# Sheet1.net
KiCad netlist of a schematic drawn in Altium Designer
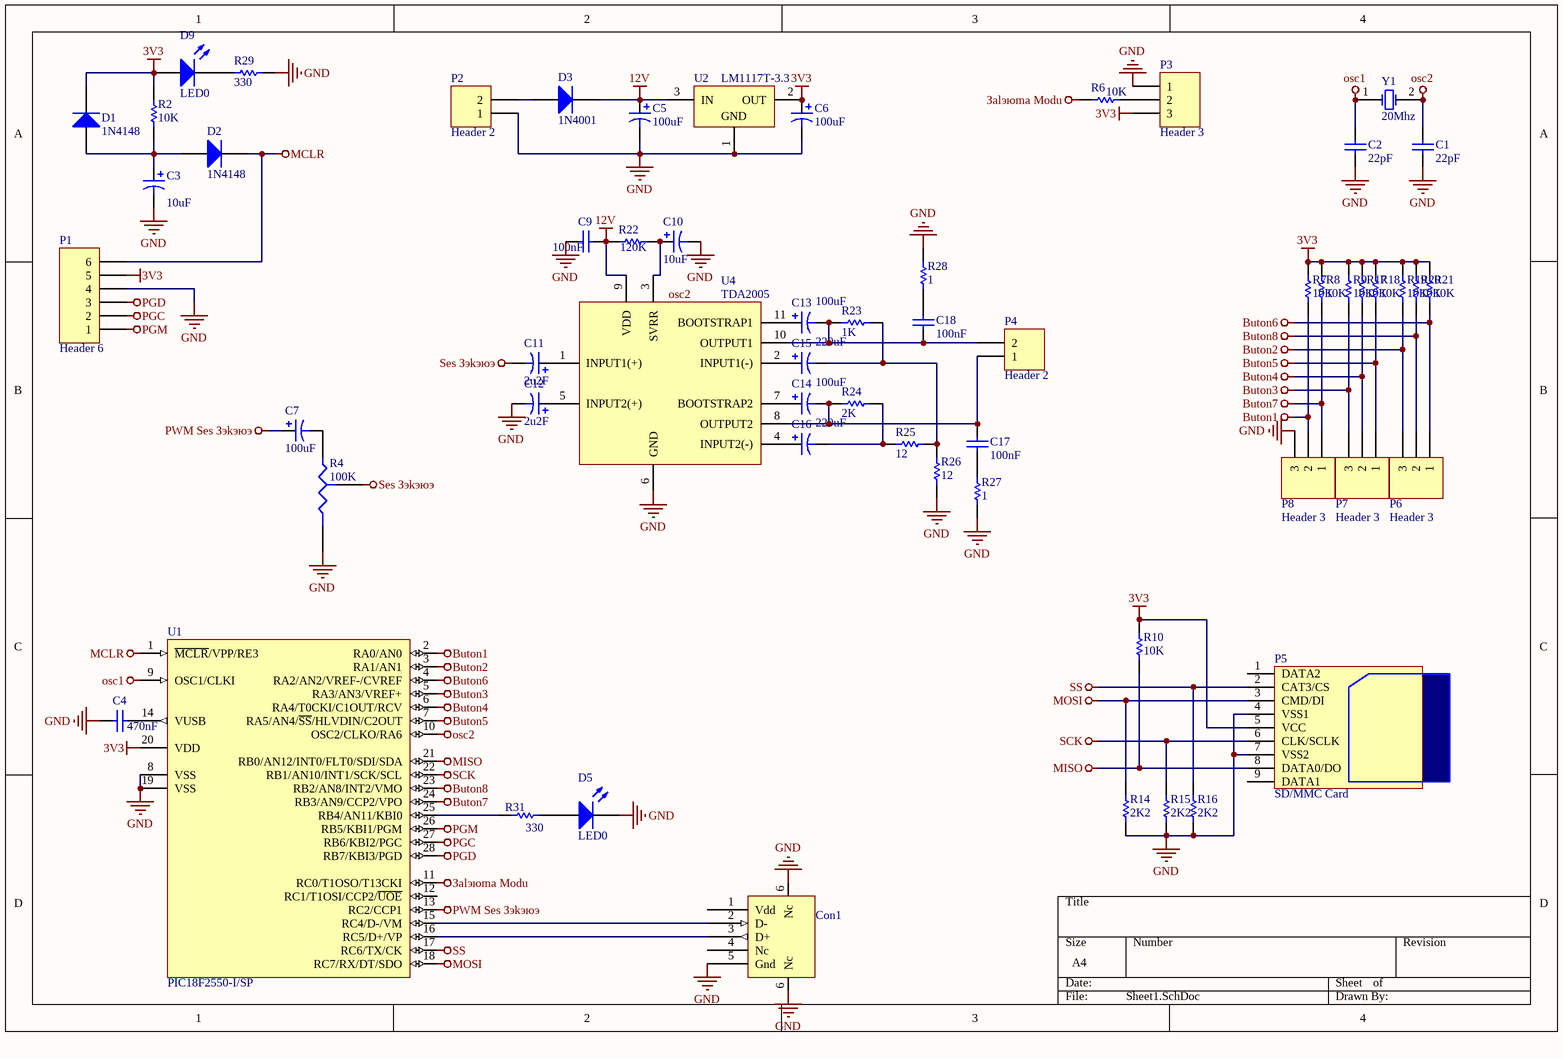
[diagram p0: Sheet1.SchDoc]

(export (version "E")
  (design (tool "Eeschema 10.0.6"))
  (components
    (comp (ref "C1")
      (value "22pF")
      (footprint "R38")
      (description "Capacitor")
      (fields (field (name "PUBLISHER") "Altium Limited"))
      (libsource (lib "Miscellaneous Devices") (part "Cap"))
    )
    (comp (ref "C2")
      (value "22pF")
      (footprint "R38")
      (description "Capacitor")
      (fields (field (name "PUBLISHER") "Altium Limited"))
      (libsource (lib "Miscellaneous Devices") (part "Cap"))
    )
    (comp (ref "C3")
      (value "10uF")
      (footprint "CAP 5x11 - 2mm")
      (description "Polarized Capacitor (Radial)")
      (fields (field (name "PUBLISHER") "Altium Limited"))
      (libsource (lib "Miscellaneous Devices") (part "Cap Pol1"))
    )
    (comp (ref "C4")
      (value "470nF")
      (footprint "Cap 5mm")
      (description "Capacitor")
      (fields (field (name "PUBLISHER") "Altium Limited"))
      (libsource (lib "Miscellaneous Devices") (part "Cap"))
    )
    (comp (ref "C5")
      (value "100uF")
      (footprint "Cap 8x11.5 - 3.5mm")
      (description "Polarized Capacitor (Radial)")
      (fields (field (name "PUBLISHER") "Altium Limited"))
      (libsource (lib "Miscellaneous Devices") (part "Cap Pol1"))
    )
    (comp (ref "C6")
      (value "100uF")
      (footprint "Cap 8x11.5 - 3.5mm")
      (description "Polarized Capacitor (Radial)")
      (fields (field (name "PUBLISHER") "Altium Limited"))
      (libsource (lib "Miscellaneous Devices") (part "Cap Pol1"))
    )
    (comp (ref "C7")
      (value "100uF")
      (footprint "Cap 8x11.5 - 3.5mm")
      (description "Polarized Capacitor (Radial)")
      (fields (field (name "PUBLISHER") "Altium Limited"))
      (libsource (lib "Miscellaneous Devices") (part "Cap Pol1"))
    )
    (comp (ref "C9")
      (value "100nF")
      (footprint "Cap 5mm")
      (description "Capacitor")
      (fields (field (name "PUBLISHER") "Altium Limited"))
      (libsource (lib "Miscellaneous Devices") (part "Cap"))
    )
    (comp (ref "C10")
      (value "10uF")
      (footprint "CAP 5x11 - 2mm")
      (description "Polarized Capacitor (Radial)")
      (fields (field (name "PUBLISHER") "Altium Limited"))
      (libsource (lib "Miscellaneous Devices") (part "Cap Pol1"))
    )
    (comp (ref "C11")
      (value "2u2F")
      (footprint "CAP 5x11 - 2mm")
      (description "Polarized Capacitor (Radial)")
      (fields (field (name "PUBLISHER") "Altium Limited"))
      (libsource (lib "Miscellaneous Devices") (part "Cap Pol1"))
    )
    (comp (ref "C12")
      (value "2u2F")
      (footprint "CAP 5x11 - 2mm")
      (description "Polarized Capacitor (Radial)")
      (fields (field (name "PUBLISHER") "Altium Limited"))
      (libsource (lib "Miscellaneous Devices") (part "Cap Pol1"))
    )
    (comp (ref "C13")
      (value "100uF")
      (footprint "Cap 8x11.5 - 3.5mm")
      (description "Polarized Capacitor (Radial)")
      (fields (field (name "PUBLISHER") "Altium Limited"))
      (libsource (lib "Miscellaneous Devices") (part "Cap Pol1"))
    )
    (comp (ref "C14")
      (value "100uF")
      (footprint "Cap 8x11.5 - 3.5mm")
      (description "Polarized Capacitor (Radial)")
      (fields (field (name "PUBLISHER") "Altium Limited"))
      (libsource (lib "Miscellaneous Devices") (part "Cap Pol1"))
    )
    (comp (ref "C15")
      (value "220uF")
      (footprint "CAP 10x12.5 - 5mm")
      (description "Polarized Capacitor (Radial)")
      (fields (field (name "PUBLISHER") "Altium Limited"))
      (libsource (lib "Miscellaneous Devices") (part "Cap Pol1"))
    )
    (comp (ref "C16")
      (value "220uF")
      (footprint "CAP 10x12.5 - 5mm")
      (description "Polarized Capacitor (Radial)")
      (fields (field (name "PUBLISHER") "Altium Limited"))
      (libsource (lib "Miscellaneous Devices") (part "Cap Pol1"))
    )
    (comp (ref "C17")
      (value "100nF")
      (footprint "Cap 5mm")
      (description "Capacitor")
      (fields (field (name "PUBLISHER") "Altium Limited"))
      (libsource (lib "Miscellaneous Devices") (part "Cap"))
    )
    (comp (ref "C18")
      (value "100nF")
      (footprint "Cap 5mm")
      (description "Capacitor")
      (fields (field (name "PUBLISHER") "Altium Limited"))
      (libsource (lib "Miscellaneous Devices") (part "Cap"))
    )
    (comp (ref "Con1")
      (value "Usb mini B")
      (footprint "USB Mini B SMD")
      (libsource (lib "Mert") (part "Usb mini B"))
    )
    (comp (ref "D1")
      (value "1N4148")
      (footprint "DO - 41")
      (description "High Conductance Fast Diode")
      (fields (field (name "PUBLISHER") "Altium Limited"))
      (libsource (lib "Miscellaneous Devices") (part "Diode 1N914"))
    )
    (comp (ref "D2")
      (value "1N4148")
      (footprint "DO - 41")
      (description "High Conductance Fast Diode")
      (fields (field (name "PUBLISHER") "Altium Limited"))
      (libsource (lib "Miscellaneous Devices") (part "Diode 1N914"))
    )
    (comp (ref "D3")
      (value "1N4001")
      (footprint "DO - 41")
      (description "Default Diode")
      (fields (field (name "PUBLISHER") "Altium Limited"))
      (libsource (lib "Miscellaneous Devices") (part "Diode"))
    )
    (comp (ref "D5")
      (value "LED0")
      (footprint "Led 4mm")
      (description "Typical INFRARED GaAs LED")
      (fields (field (name "PUBLISHER") "Altium Limited"))
      (libsource (lib "Miscellaneous Devices") (part "LED0"))
    )
    (comp (ref "D9")
      (value "LED0")
      (footprint "Led 4mm")
      (description "Typical INFRARED GaAs LED")
      (fields (field (name "PUBLISHER") "Altium Limited"))
      (libsource (lib "Miscellaneous Devices") (part "LED0"))
    )
    (comp (ref "P1")
      (value "Header 6")
      (footprint "Header 6 way")
      (description "Header, 6-Pin")
      (fields (field (name "PUBLISHER") "Altium Limited"))
      (libsource (lib "Miscellaneous Connectors") (part "Header 6"))
    )
    (comp (ref "P2")
      (value "Header 2")
      (footprint "Klemens 3P")
      (description "Header, 2-Pin")
      (fields (field (name "PUBLISHER") "Altium Limited"))
      (libsource (lib "") (part "Header 2_1"))
    )
    (comp (ref "P3")
      (value "Header 3")
      (footprint "HDR1X3")
      (description "Header, 3-Pin")
      (fields (field (name "PUBLISHER") "Altium Limited"))
      (libsource (lib "") (part "Header 3_1"))
    )
    (comp (ref "P4")
      (value "Header 2")
      (footprint "Klemens 3P")
      (description "Header, 2-Pin")
      (fields (field (name "PUBLISHER") "Altium Limited"))
      (libsource (lib "Miscellaneous Connectors") (part "Header 2"))
    )
    (comp (ref "P5") (value "SD/MMC Card") (footprint "SD/MMC") (libsource (lib "Mert") (part "MMC Kart")))
    (comp (ref "P6")
      (value "Header 3")
      (footprint "Klemens 3P")
      (description "Header, 3-Pin")
      (fields (field (name "PUBLISHER") "Altium Limited"))
      (libsource (lib "Miscellaneous Connectors") (part "Header 3"))
    )
    (comp (ref "P7")
      (value "Header 3")
      (footprint "Klemens 3P")
      (description "Header, 3-Pin")
      (fields (field (name "PUBLISHER") "Altium Limited"))
      (libsource (lib "Miscellaneous Connectors") (part "Header 3"))
    )
    (comp (ref "P8")
      (value "Header 3")
      (footprint "Klemens 3P")
      (description "Header, 3-Pin")
      (fields (field (name "PUBLISHER") "Altium Limited"))
      (libsource (lib "Miscellaneous Connectors") (part "Header 3"))
    )
    (comp (ref "R2")
      (value "10K")
      (footprint "Dip 0.3 inc")
      (description "Resistor")
      (fields (field (name "PUBLISHER") "Altium Limited"))
      (libsource (lib "Miscellaneous Devices") (part "Res1"))
    )
    (comp (ref "R4")
      (value "100K")
      (footprint "Trimpot dik")
      (description "Tapped Resistor")
      (fields (field (name "PUBLISHER") "Altium Limited"))
      (libsource (lib "Miscellaneous Devices") (part "Res Tap"))
    )
    (comp (ref "R6")
      (value "10K")
      (footprint "Dip 0.3 inc")
      (description "Resistor")
      (fields (field (name "PUBLISHER") "Altium Limited"))
      (libsource (lib "Miscellaneous Devices") (part "Res1"))
    )
    (comp (ref "R7")
      (value "10K")
      (footprint "Dip 0.3 inc")
      (description "Resistor")
      (fields (field (name "PUBLISHER") "Altium Limited"))
      (libsource (lib "Miscellaneous Devices") (part "Res1"))
    )
    (comp (ref "R8")
      (value "10K")
      (footprint "Dip 0.3 inc")
      (description "Resistor")
      (fields (field (name "PUBLISHER") "Altium Limited"))
      (libsource (lib "Miscellaneous Devices") (part "Res1"))
    )
    (comp (ref "R9")
      (value "10K")
      (footprint "Dip 0.3 inc")
      (description "Resistor")
      (fields (field (name "PUBLISHER") "Altium Limited"))
      (libsource (lib "Miscellaneous Devices") (part "Res1"))
    )
    (comp (ref "R10")
      (value "10K")
      (footprint "Dip 0.3 inc")
      (description "Resistor")
      (fields (field (name "PUBLISHER") "Altium Limited"))
      (libsource (lib "Miscellaneous Devices") (part "Res1"))
    )
    (comp (ref "R14")
      (value "2K2")
      (footprint "Dip 0.3 inc")
      (description "Resistor")
      (fields (field (name "PUBLISHER") "Altium Limited"))
      (libsource (lib "Miscellaneous Devices") (part "Res1"))
    )
    (comp (ref "R15")
      (value "2K2")
      (footprint "Dip 0.3 inc")
      (description "Resistor")
      (fields (field (name "PUBLISHER") "Altium Limited"))
      (libsource (lib "Miscellaneous Devices") (part "Res1"))
    )
    (comp (ref "R16")
      (value "2K2")
      (footprint "Dip 0.3 inc")
      (description "Resistor")
      (fields (field (name "PUBLISHER") "Altium Limited"))
      (libsource (lib "Miscellaneous Devices") (part "Res1"))
    )
    (comp (ref "R17")
      (value "10K")
      (footprint "Dip 0.3 inc")
      (description "Resistor")
      (fields (field (name "PUBLISHER") "Altium Limited"))
      (libsource (lib "Miscellaneous Devices") (part "Res1"))
    )
    (comp (ref "R18")
      (value "10K")
      (footprint "Dip 0.3 inc")
      (description "Resistor")
      (fields (field (name "PUBLISHER") "Altium Limited"))
      (libsource (lib "Miscellaneous Devices") (part "Res1"))
    )
    (comp (ref "R19")
      (value "10K")
      (footprint "Dip 0.3 inc")
      (description "Resistor")
      (fields (field (name "PUBLISHER") "Altium Limited"))
      (libsource (lib "Miscellaneous Devices") (part "Res1"))
    )
    (comp (ref "R20")
      (value "10K")
      (footprint "Dip 0.3 inc")
      (description "Resistor")
      (fields (field (name "PUBLISHER") "Altium Limited"))
      (libsource (lib "Miscellaneous Devices") (part "Res1"))
    )
    (comp (ref "R21")
      (value "10K")
      (footprint "Dip 0.3 inc")
      (description "Resistor")
      (fields (field (name "PUBLISHER") "Altium Limited"))
      (libsource (lib "Miscellaneous Devices") (part "Res1"))
    )
    (comp (ref "R22")
      (value "120K")
      (footprint "Dip 0.3 inc")
      (description "Resistor")
      (fields (field (name "PUBLISHER") "Altium Limited"))
      (libsource (lib "Miscellaneous Devices") (part "Res1"))
    )
    (comp (ref "R23")
      (value "1K")
      (footprint "Dip 0.3 inc")
      (description "Resistor")
      (fields (field (name "PUBLISHER") "Altium Limited"))
      (libsource (lib "Miscellaneous Devices") (part "Res1"))
    )
    (comp (ref "R24")
      (value "2K")
      (footprint "Dip 0.3 inc")
      (description "Resistor")
      (fields (field (name "PUBLISHER") "Altium Limited"))
      (libsource (lib "Miscellaneous Devices") (part "Res1"))
    )
    (comp (ref "R25")
      (value "12")
      (footprint "Dip 0.3 inc")
      (description "Resistor")
      (fields (field (name "PUBLISHER") "Altium Limited"))
      (libsource (lib "Miscellaneous Devices") (part "Res1"))
    )
    (comp (ref "R26")
      (value "12")
      (footprint "Dip 0.3 inc")
      (description "Resistor")
      (fields (field (name "PUBLISHER") "Altium Limited"))
      (libsource (lib "Miscellaneous Devices") (part "Res1"))
    )
    (comp (ref "R27")
      (value "1")
      (footprint "Dip 0.3 inc")
      (description "Resistor")
      (fields (field (name "PUBLISHER") "Altium Limited"))
      (libsource (lib "Miscellaneous Devices") (part "Res1"))
    )
    (comp (ref "R28")
      (value "1")
      (footprint "Dip 0.3 inc")
      (description "Resistor")
      (fields (field (name "PUBLISHER") "Altium Limited"))
      (libsource (lib "Miscellaneous Devices") (part "Res1"))
    )
    (comp (ref "R29")
      (value "330")
      (footprint "Dip 0.3 inc")
      (description "Resistor")
      (fields (field (name "PUBLISHER") "Altium Limited"))
      (libsource (lib "Miscellaneous Devices") (part "Res1"))
    )
    (comp (ref "R31")
      (value "330")
      (footprint "Dip 0.3 inc")
      (description "Resistor")
      (fields (field (name "PUBLISHER") "Altium Limited"))
      (libsource (lib "Miscellaneous Devices") (part "Res1"))
    )
    (comp (ref "U1")
      (value "PIC18F2550-I/SP")
      (footprint "SPDIP300-SP28")
      (fields (field (name "PUBLISHER") "Altium Limited"))
      (libsource (lib "Microchip Microcontroller 8-Bit PIC18") (part "PIC18F2550-I/SP"))
    )
    (comp (ref "U2")
      (value "LM1117T-3.3")
      (footprint "T03B")
      (description "800mA Low-Dropout Linear Regulator")
      (fields
        (field (name "MANUFACTURER") "National Semiconductor")
        (field (name "DIGIKEYPARTNUMBER") "LM1117T-3.3-ND")
        (field (name "PUBLISHER") "Altium Limited")
      )
      (libsource (lib "NSC LDO") (part "LM1117T-3.3"))
    )
    (comp (ref "U4") (value "TDA2005") (footprint "Multiwatt11") (libsource (lib "Mert") (part "TDA2005")))
    (comp (ref "Y1")
      (value "20Mhz")
      (footprint "Kristal")
      (description "Crystal Oscillator")
      (fields (field (name "PUBLISHER") "Altium Limited"))
      (libsource (lib "Miscellaneous Devices") (part "XTAL"))
    )
  )
  (nets
    (net (code "1") (name "3V3") (class "Default")
      (node (ref "C6") (pin "1") (pinfunction "1_1") (pintype "passive"))
      (node (ref "D1") (pin "2") (pinfunction "K_2") (pintype "passive"))
      (node (ref "D9") (pin "1") (pinfunction "A_1") (pintype "passive"))
      (node (ref "P1") (pin "5") (pinfunction "5_5") (pintype "passive"))
      (node (ref "P3") (pin "3") (pinfunction "3_3") (pintype "passive"))
      (node (ref "P5") (pin "5") (pinfunction "VCC_5") (pintype "passive"))
      (node (ref "R10") (pin "1") (pinfunction "1_1") (pintype "passive"))
      (node (ref "R17") (pin "1") (pinfunction "1_1") (pintype "passive"))
      (node (ref "R18") (pin "1") (pinfunction "1_1") (pintype "passive"))
      (node (ref "R19") (pin "1") (pinfunction "1_1") (pintype "passive"))
      (node (ref "R2") (pin "2") (pinfunction "2_2") (pintype "passive"))
      (node (ref "R20") (pin "1") (pinfunction "1_1") (pintype "passive"))
      (node (ref "R21") (pin "1") (pinfunction "1_1") (pintype "passive"))
      (node (ref "R7") (pin "1") (pinfunction "1_1") (pintype "passive"))
      (node (ref "R8") (pin "1") (pinfunction "1_1") (pintype "passive"))
      (node (ref "R9") (pin "1") (pinfunction "1_1") (pintype "passive"))
      (node (ref "U1") (pin "20") (pinfunction "VDD_20") (pintype "power_in"))
      (node (ref "U2") (pin "2") (pinfunction "OUT_2") (pintype "power_in"))
    )
    (net (code "2") (name "12V") (class "Default")
      (node (ref "C5") (pin "1") (pinfunction "1_1") (pintype "passive"))
      (node (ref "C9") (pin "2") (pinfunction "2_2") (pintype "passive"))
      (node (ref "D3") (pin "2") (pinfunction "K_2") (pintype "passive"))
      (node (ref "R22") (pin "2") (pinfunction "2_2") (pintype "passive"))
      (node (ref "U2") (pin "3") (pinfunction "IN_3") (pintype "power_in"))
      (node (ref "U4") (pin "9") (pinfunction "VDD_9") (pintype "passive"))
    )
    (net (code "3") (name "Buton1") (class "Default")
      (node (ref "P8") (pin "2") (pinfunction "2_2") (pintype "passive"))
      (node (ref "R7") (pin "2") (pinfunction "2_2") (pintype "passive"))
      (node (ref "U1") (pin "2") (pinfunction "RA0/AN0_2") (pintype "bidirectional"))
    )
    (net (code "4") (name "Buton2") (class "Default")
      (node (ref "P6") (pin "3") (pinfunction "3_3") (pintype "passive"))
      (node (ref "R19") (pin "2") (pinfunction "2_2") (pintype "passive"))
      (node (ref "U1") (pin "3") (pinfunction "RA1/AN1_3") (pintype "bidirectional"))
    )
    (net (code "5") (name "Buton3") (class "Default")
      (node (ref "P7") (pin "3") (pinfunction "3_3") (pintype "passive"))
      (node (ref "R9") (pin "2") (pinfunction "2_2") (pintype "passive"))
      (node (ref "U1") (pin "5") (pinfunction "RA3/AN3/VREF+_5") (pintype "bidirectional"))
    )
    (net (code "6") (name "Buton4") (class "Default")
      (node (ref "P7") (pin "2") (pinfunction "2_2") (pintype "passive"))
      (node (ref "R17") (pin "2") (pinfunction "2_2") (pintype "passive"))
      (node (ref "U1") (pin "6") (pinfunction "RA4/T0CKI/C1OUT/RCV_6") (pintype "bidirectional"))
    )
    (net (code "7") (name "Buton5") (class "Default")
      (node (ref "P7") (pin "1") (pinfunction "1_1") (pintype "passive"))
      (node (ref "R18") (pin "2") (pinfunction "2_2") (pintype "passive"))
      (node (ref "U1") (pin "7") (pinfunction "RA5/AN4/~{SS}/HLVDIN/C2OUT_7") (pintype "bidirectional"))
    )
    (net (code "8") (name "Buton6") (class "Default")
      (node (ref "P6") (pin "1") (pinfunction "1_1") (pintype "passive"))
      (node (ref "R21") (pin "2") (pinfunction "2_2") (pintype "passive"))
      (node (ref "U1") (pin "4") (pinfunction "RA2/AN2/VREF-/CVREF_4") (pintype "bidirectional"))
    )
    (net (code "9") (name "Buton7") (class "Default")
      (node (ref "P8") (pin "1") (pinfunction "1_1") (pintype "passive"))
      (node (ref "R8") (pin "2") (pinfunction "2_2") (pintype "passive"))
      (node (ref "U1") (pin "24") (pinfunction "RB3/AN9/CCP2/VPO_24") (pintype "bidirectional"))
    )
    (net (code "10") (name "Buton8") (class "Default")
      (node (ref "P6") (pin "2") (pinfunction "2_2") (pintype "passive"))
      (node (ref "R20") (pin "2") (pinfunction "2_2") (pintype "passive"))
      (node (ref "U1") (pin "23") (pinfunction "RB2/AN8/INT2/VMO_23") (pintype "bidirectional"))
    )
    (net (code "11") (name "GND") (class "Default")
      (node (ref "C1") (pin "1") (pinfunction "1_1") (pintype "passive"))
      (node (ref "C10") (pin "2") (pinfunction "2_2") (pintype "passive"))
      (node (ref "C12") (pin "2") (pinfunction "2_2") (pintype "passive"))
      (node (ref "C2") (pin "1") (pinfunction "1_1") (pintype "passive"))
      (node (ref "C3") (pin "2") (pinfunction "2_2") (pintype "passive"))
      (node (ref "C4") (pin "1") (pinfunction "1_1") (pintype "passive"))
      (node (ref "C5") (pin "2") (pinfunction "2_2") (pintype "passive"))
      (node (ref "C6") (pin "2") (pinfunction "2_2") (pintype "passive"))
      (node (ref "C9") (pin "1") (pinfunction "1_1") (pintype "passive"))
      (node (ref "Con1") (pin "5") (pinfunction "Gnd_5") (pintype "power_in"))
      (node (ref "Con1") (pin "6") (pinfunction "Nc_6") (pintype "passive"))
      (node (ref "D5") (pin "2") (pinfunction "K_2") (pintype "passive"))
      (node (ref "P1") (pin "4") (pinfunction "4_4") (pintype "passive"))
      (node (ref "P2") (pin "1") (pinfunction "1_1") (pintype "passive"))
      (node (ref "P3") (pin "1") (pinfunction "1_1") (pintype "passive"))
      (node (ref "P5") (pin "4") (pinfunction "VSS1_4") (pintype "passive"))
      (node (ref "P5") (pin "7") (pinfunction "VSS2_7") (pintype "passive"))
      (node (ref "P8") (pin "3") (pinfunction "3_3") (pintype "passive"))
      (node (ref "R14") (pin "1") (pinfunction "1_1") (pintype "passive"))
      (node (ref "R15") (pin "1") (pinfunction "1_1") (pintype "passive"))
      (node (ref "R16") (pin "1") (pinfunction "1_1") (pintype "passive"))
      (node (ref "R26") (pin "1") (pinfunction "1_1") (pintype "passive"))
      (node (ref "R27") (pin "1") (pinfunction "1_1") (pintype "passive"))
      (node (ref "R28") (pin "1") (pinfunction "1_1") (pintype "passive"))
      (node (ref "R29") (pin "2") (pinfunction "2_2") (pintype "passive"))
      (node (ref "R4") (pin "2") (pinfunction "B_2") (pintype "passive"))
      (node (ref "U1") (pin "19") (pinfunction "VSS_19") (pintype "power_in"))
      (node (ref "U1") (pin "8") (pinfunction "VSS_8") (pintype "power_in"))
      (node (ref "U2") (pin "1") (pinfunction "GND_1") (pintype "power_in"))
      (node (ref "U4") (pin "6") (pinfunction "GND_6") (pintype "passive"))
    )
    (net (code "12") (name "MCLR") (class "Default")
      (node (ref "D2") (pin "2") (pinfunction "K_2") (pintype "passive"))
      (node (ref "P1") (pin "6") (pinfunction "6_6") (pintype "passive"))
      (node (ref "U1") (pin "1") (pinfunction "~{MCLR}/VPP/RE3_1") (pintype "input"))
    )
    (net (code "13") (name "MISO") (class "Default")
      (node (ref "P5") (pin "8") (pinfunction "DATA0/DO_8") (pintype "passive"))
      (node (ref "R10") (pin "2") (pinfunction "2_2") (pintype "passive"))
      (node (ref "U1") (pin "21") (pinfunction "RB0/AN12/INT0/FLT0/SDI/SDA_21") (pintype "bidirectional"))
    )
    (net (code "14") (name "MOSI") (class "Default")
      (node (ref "P5") (pin "3") (pinfunction "CMD/DI_3") (pintype "passive"))
      (node (ref "R14") (pin "2") (pinfunction "2_2") (pintype "passive"))
      (node (ref "U1") (pin "18") (pinfunction "RC7/RX/DT/SDO_18") (pintype "bidirectional"))
    )
    (net (code "15") (name "Net-(C15-Pad2)") (class "Default")
      (node (ref "C15") (pin "2") (pinfunction "2_2") (pintype "passive"))
      (node (ref "R23") (pin "2") (pinfunction "2_2") (pintype "passive"))
      (node (ref "R25") (pin "2") (pinfunction "2_2") (pintype "passive"))
      (node (ref "R26") (pin "2") (pinfunction "2_2") (pintype "passive"))
    )
    (net (code "16") (name "Net-(C16-Pad2)") (class "Default")
      (node (ref "C16") (pin "2") (pinfunction "2_2") (pintype "passive"))
      (node (ref "R24") (pin "2") (pinfunction "2_2") (pintype "passive"))
      (node (ref "R25") (pin "1") (pinfunction "1_1") (pintype "passive"))
    )
    (net (code "17") (name "Net-(C17-Pad1)") (class "Default")
      (node (ref "C17") (pin "1") (pinfunction "1_1") (pintype "passive"))
      (node (ref "R27") (pin "2") (pinfunction "2_2") (pintype "passive"))
    )
    (net (code "18") (name "Net-(C18-Pad1)") (class "Default")
      (node (ref "C18") (pin "1") (pinfunction "1_1") (pintype "passive"))
      (node (ref "R28") (pin "2") (pinfunction "2_2") (pintype "passive"))
    )
    (net (code "19") (name "Net-(Con1-D+)") (class "Default")
      (node (ref "Con1") (pin "3") (pinfunction "D+_3") (pintype "output"))
      (node (ref "U1") (pin "16") (pinfunction "RC5/D+/VP_16") (pintype "bidirectional"))
    )
    (net (code "20") (name "Net-(Con1-D-)") (class "Default")
      (node (ref "Con1") (pin "2") (pinfunction "D-_2") (pintype "input"))
      (node (ref "U1") (pin "15") (pinfunction "RC4/D-/VM_15") (pintype "bidirectional"))
    )
    (net (code "21") (name "Net-(D1-A)") (class "Default")
      (node (ref "C3") (pin "1") (pinfunction "1_1") (pintype "passive"))
      (node (ref "D1") (pin "1") (pinfunction "A_1") (pintype "passive"))
      (node (ref "D2") (pin "1") (pinfunction "A_1") (pintype "passive"))
      (node (ref "R2") (pin "1") (pinfunction "1_1") (pintype "passive"))
    )
    (net (code "22") (name "Net-(D3-A)") (class "Default")
      (node (ref "D3") (pin "1") (pinfunction "A_1") (pintype "passive"))
      (node (ref "P2") (pin "2") (pinfunction "2_2") (pintype "passive"))
    )
    (net (code "23") (name "Net-(D5-A)") (class "Default")
      (node (ref "D5") (pin "1") (pinfunction "A_1") (pintype "passive"))
      (node (ref "R31") (pin "1") (pinfunction "1_1") (pintype "passive"))
    )
    (net (code "24") (name "Net-(D9-K)") (class "Default")
      (node (ref "D9") (pin "2") (pinfunction "K_2") (pintype "passive"))
      (node (ref "R29") (pin "1") (pinfunction "1_1") (pintype "passive"))
    )
    (net (code "25") (name "Net-(P3-Pad2)") (class "Default")
      (node (ref "P3") (pin "2") (pinfunction "2_2") (pintype "passive"))
      (node (ref "R6") (pin "1") (pinfunction "1_1") (pintype "passive"))
    )
    (net (code "26") (name "Net-(R4-A)") (class "Default")
      (node (ref "C7") (pin "2") (pinfunction "2_2") (pintype "passive"))
      (node (ref "R4") (pin "1") (pinfunction "A_1") (pintype "passive"))
    )
    (net (code "27") (name "Net-(U1-RB4{slash}AN11{slash}KBI0)") (class "Default")
      (node (ref "R31") (pin "2") (pinfunction "2_2") (pintype "passive"))
      (node (ref "U1") (pin "25") (pinfunction "RB4/AN11/KBI0_25") (pintype "bidirectional"))
    )
    (net (code "28") (name "Net-(U1-VUSB)") (class "Default")
      (node (ref "C4") (pin "2") (pinfunction "2_2") (pintype "passive"))
      (node (ref "U1") (pin "14") (pinfunction "VUSB_14") (pintype "output"))
    )
    (net (code "29") (name "Net-(U4-BOOTSTRAP1)") (class "Default")
      (node (ref "C13") (pin "1") (pinfunction "1_1") (pintype "passive"))
      (node (ref "U4") (pin "11") (pinfunction "BOOTSTRAP1_11") (pintype "passive"))
    )
    (net (code "30") (name "Net-(U4-BOOTSTRAP2)") (class "Default")
      (node (ref "C14") (pin "1") (pinfunction "1_1") (pintype "passive"))
      (node (ref "U4") (pin "7") (pinfunction "BOOTSTRAP2_7") (pintype "passive"))
    )
    (net (code "31") (name "Net-(U4-INPUT1(+))") (class "Default")
      (node (ref "C11") (pin "1") (pinfunction "1_1") (pintype "passive"))
      (node (ref "U4") (pin "1") (pinfunction "INPUT1(+)_1") (pintype "passive"))
    )
    (net (code "32") (name "Net-(U4-INPUT1(-))") (class "Default")
      (node (ref "C15") (pin "1") (pinfunction "1_1") (pintype "passive"))
      (node (ref "U4") (pin "2") (pinfunction "INPUT1(-)_2") (pintype "passive"))
    )
    (net (code "33") (name "Net-(U4-INPUT2(+))") (class "Default")
      (node (ref "C12") (pin "1") (pinfunction "1_1") (pintype "passive"))
      (node (ref "U4") (pin "5") (pinfunction "INPUT2(+)_5") (pintype "passive"))
    )
    (net (code "34") (name "Net-(U4-INPUT2(-))") (class "Default")
      (node (ref "C16") (pin "1") (pinfunction "1_1") (pintype "passive"))
      (node (ref "U4") (pin "4") (pinfunction "INPUT2(-)_4") (pintype "passive"))
    )
    (net (code "35") (name "Net-(U4-OUTPUT1)") (class "Default")
      (node (ref "C13") (pin "2") (pinfunction "2_2") (pintype "passive"))
      (node (ref "C18") (pin "2") (pinfunction "2_2") (pintype "passive"))
      (node (ref "P4") (pin "2") (pinfunction "2_2") (pintype "passive"))
      (node (ref "R23") (pin "1") (pinfunction "1_1") (pintype "passive"))
      (node (ref "U4") (pin "10") (pinfunction "OUTPUT1_10") (pintype "passive"))
    )
    (net (code "36") (name "Net-(U4-OUTPUT2)") (class "Default")
      (node (ref "C14") (pin "2") (pinfunction "2_2") (pintype "passive"))
      (node (ref "C17") (pin "2") (pinfunction "2_2") (pintype "passive"))
      (node (ref "P4") (pin "1") (pinfunction "1_1") (pintype "passive"))
      (node (ref "R24") (pin "1") (pinfunction "1_1") (pintype "passive"))
      (node (ref "U4") (pin "8") (pinfunction "OUTPUT2_8") (pintype "passive"))
    )
    (net (code "37") (name "Net-(U4-SVRR)") (class "Default")
      (node (ref "C10") (pin "1") (pinfunction "1_1") (pintype "passive"))
      (node (ref "R22") (pin "1") (pinfunction "1_1") (pintype "passive"))
      (node (ref "U4") (pin "3") (pinfunction "SVRR_3") (pintype "passive"))
    )
    (net (code "38") (name "PGC") (class "Default")
      (node (ref "P1") (pin "2") (pinfunction "2_2") (pintype "passive"))
      (node (ref "U1") (pin "27") (pinfunction "RB6/KBI2/PGC_27") (pintype "bidirectional"))
    )
    (net (code "39") (name "PGD") (class "Default")
      (node (ref "P1") (pin "3") (pinfunction "3_3") (pintype "passive"))
      (node (ref "U1") (pin "28") (pinfunction "RB7/KBI3/PGD_28") (pintype "bidirectional"))
    )
    (net (code "40") (name "PGM") (class "Default")
      (node (ref "P1") (pin "1") (pinfunction "1_1") (pintype "passive"))
      (node (ref "U1") (pin "26") (pinfunction "RB5/KBI1/PGM_26") (pintype "bidirectional"))
    )
    (net (code "41") (name "PWM Ses Çýkýþý") (class "Default")
      (node (ref "C7") (pin "1") (pinfunction "1_1") (pintype "passive"))
      (node (ref "U1") (pin "13") (pinfunction "RC2/CCP1_13") (pintype "bidirectional"))
    )
    (net (code "42") (name "SCK") (class "Default")
      (node (ref "P5") (pin "6") (pinfunction "CLK/SCLK_6") (pintype "passive"))
      (node (ref "R15") (pin "2") (pinfunction "2_2") (pintype "passive"))
      (node (ref "U1") (pin "22") (pinfunction "RB1/AN10/INT1/SCK/SCL_22") (pintype "bidirectional"))
    )
    (net (code "43") (name "SS") (class "Default")
      (node (ref "P5") (pin "2") (pinfunction "CAT3/CS_2") (pintype "passive"))
      (node (ref "R16") (pin "2") (pinfunction "2_2") (pintype "passive"))
      (node (ref "U1") (pin "17") (pinfunction "RC6/TX/CK_17") (pintype "bidirectional"))
    )
    (net (code "44") (name "Ses Çýkýþý") (class "Default")
      (node (ref "C11") (pin "2") (pinfunction "2_2") (pintype "passive"))
      (node (ref "R4") (pin "3") (pinfunction "TAP_3") (pintype "passive"))
    )
    (net (code "45") (name "osc1") (class "Default")
      (node (ref "C2") (pin "2") (pinfunction "2_2") (pintype "passive"))
      (node (ref "U1") (pin "9") (pinfunction "OSC1/CLKI_9") (pintype "input"))
      (node (ref "Y1") (pin "1") (pinfunction "OSC1_1") (pintype "passive"))
    )
    (net (code "46") (name "osc2") (class "Default")
      (node (ref "C1") (pin "2") (pinfunction "2_2") (pintype "passive"))
      (node (ref "U1") (pin "10") (pinfunction "OSC2/CLKO/RA6_10") (pintype "bidirectional"))
      (node (ref "Y1") (pin "2") (pinfunction "OSC2_2") (pintype "passive"))
    )
    (net (code "47") (name "unconnected-(Con1-Nc-Pad4)") (class "Default")
      (node (ref "Con1") (pin "4") (pinfunction "Nc_4") (pintype "power_in"))
    )
    (net (code "48") (name "unconnected-(Con1-Vdd-Pad1)") (class "Default")
      (node (ref "Con1") (pin "1") (pinfunction "Vdd_1") (pintype "passive"))
    )
    (net (code "49") (name "unconnected-(P5-DATA1-Pad9)") (class "Default")
      (node (ref "P5") (pin "9") (pinfunction "DATA1_9") (pintype "passive"))
    )
    (net (code "50") (name "unconnected-(P5-DATA2-Pad1)") (class "Default")
      (node (ref "P5") (pin "1") (pinfunction "DATA2_1") (pintype "passive"))
    )
    (net (code "51") (name "unconnected-(U1-RC1{slash}T1OSI{slash}CCP2{slash}~{UOE}-Pad12)") (class "Default")
      (node (ref "U1") (pin "12") (pinfunction "RC1/T1OSI/CCP2/~{UOE}_12") (pintype "bidirectional"))
    )
    (net (code "52") (name "Çalýþma Modu") (class "Default")
      (node (ref "R6") (pin "2") (pinfunction "2_2") (pintype "passive"))
      (node (ref "U1") (pin "11") (pinfunction "RC0/T1OSO/T13CKI_11") (pintype "bidirectional"))
    )
  )
)
